# Gateway.net
KiCad netlist of a schematic drawn in EAGLE
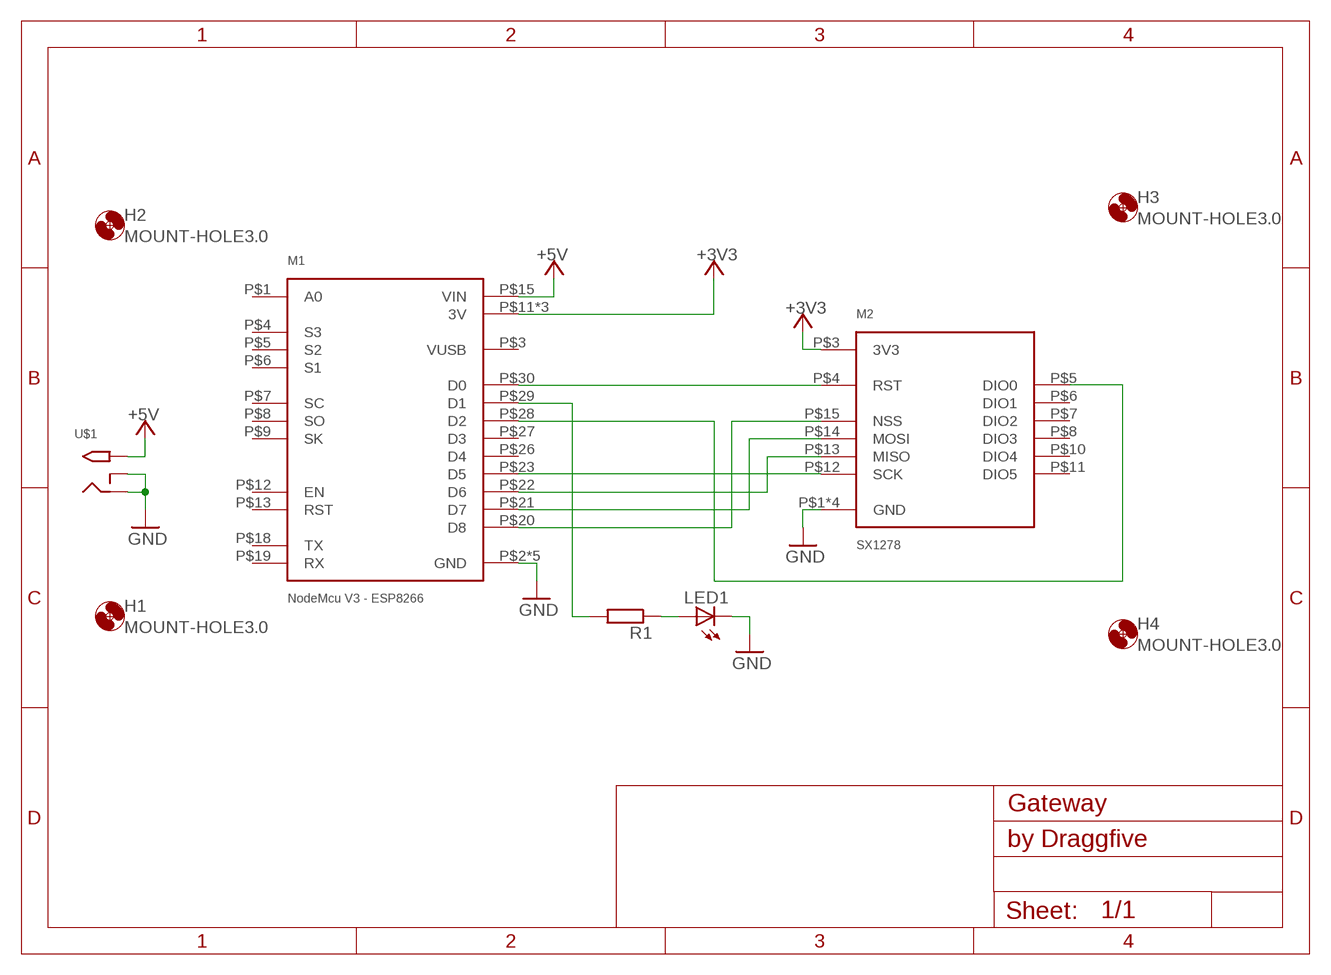
[diagram p0: schematic, sheet 1]

(export (version "E")
  (design (tool "Eeschema 10.0.6"))
  (components
    (comp (ref "H1")
      (value "MOUNT-HOLE3.0")
      (footprint "eagle-import:3,0")
      (libsource (lib "eagle-import") (part "MOUNT-HOLE3.0"))
    )
    (comp (ref "H2")
      (value "MOUNT-HOLE3.0")
      (footprint "eagle-import:3,0")
      (libsource (lib "eagle-import") (part "MOUNT-HOLE3.0"))
    )
    (comp (ref "H3")
      (value "MOUNT-HOLE3.0")
      (footprint "eagle-import:3,0")
      (libsource (lib "eagle-import") (part "MOUNT-HOLE3.0"))
    )
    (comp (ref "H4")
      (value "MOUNT-HOLE3.0")
      (footprint "eagle-import:3,0")
      (libsource (lib "eagle-import") (part "MOUNT-HOLE3.0"))
    )
    (comp (ref "LED1")
      (value "LED5MM")
      (footprint "eagle-import:LED5MM")
      (libsource (lib "eagle-import") (part "LED5MM"))
    )
    (comp (ref "M1")
      (value "NodeMcu V3 - ESP8266")
      (footprint "eagle-import:NODEMCU_V3")
      (libsource (lib "eagle-import") (part "NODEMCU_V3"))
    )
    (comp (ref "M2")
      (value "SX1278")
      (footprint "eagle-import:SX1278")
      (libsource (lib "eagle-import") (part "SX1278"))
    )
    (comp (ref "R1")
      (value "R-EU_0207/10")
      (footprint "eagle-import:0207_10")
      (libsource (lib "eagle-import") (part "R-EU_0207/10"))
    )
    (comp (ref "U$1")
      (value "2.1MMJACKTHM")
      (footprint "eagle-import:PJ-102A")
      (libsource (lib "eagle-import") (part "2.1MMJACKTHM"))
    )
  )
  (nets
    (net (code "1") (name "+3V3") (class "Default")
      (node (ref "M1") (pin "P$11") (pinfunction "3V_P$11") (pintype "bidirectional"))
      (node (ref "M1") (pin "P$16") (pinfunction "3V_P$16") (pintype "bidirectional"))
      (node (ref "M1") (pin "P$25") (pinfunction "3V_P$25") (pintype "bidirectional"))
      (node (ref "M2") (pin "P$3") (pinfunction "3V3_P$3") (pintype "bidirectional"))
    )
    (net (code "2") (name "+5V") (class "Default")
      (node (ref "M1") (pin "P$15") (pinfunction "VIN_P$15") (pintype "bidirectional"))
      (node (ref "U$1") (pin "TIP") (pinfunction "TIP_TIP") (pintype "bidirectional"))
    )
    (net (code "3") (name "GND") (class "Default")
      (node (ref "LED1") (pin "K") (pinfunction "C_K") (pintype "passive"))
      (node (ref "M1") (pin "P$10") (pinfunction "GND_P$10") (pintype "bidirectional"))
      (node (ref "M1") (pin "P$14") (pinfunction "GND_P$14") (pintype "bidirectional"))
      (node (ref "M1") (pin "P$17") (pinfunction "GND_P$17") (pintype "bidirectional"))
      (node (ref "M1") (pin "P$2") (pinfunction "GND_P$2") (pintype "bidirectional"))
      (node (ref "M1") (pin "P$24") (pinfunction "GND_P$24") (pintype "bidirectional"))
      (node (ref "M2") (pin "P$1") (pinfunction "GND_P$1") (pintype "bidirectional"))
      (node (ref "M2") (pin "P$16") (pinfunction "GND_P$16") (pintype "bidirectional"))
      (node (ref "M2") (pin "P$2") (pinfunction "GND_P$2") (pintype "bidirectional"))
      (node (ref "M2") (pin "P$9") (pinfunction "GND_P$9") (pintype "bidirectional"))
      (node (ref "U$1") (pin "RING") (pinfunction "RING_RING") (pintype "bidirectional"))
      (node (ref "U$1") (pin "RING_SW") (pinfunction "RING_SW_RING_SW") (pintype "bidirectional"))
    )
    (net (code "4") (name "Net-(LED1-PadA)") (class "Default")
      (node (ref "LED1") (pin "A") (pinfunction "A_A") (pintype "passive"))
      (node (ref "R1") (pin "1") (pinfunction "1_1") (pintype "passive"))
    )
    (net (code "5") (name "Net-(M1-D0)") (class "Default")
      (node (ref "M1") (pin "P$30") (pinfunction "D0_P$30") (pintype "bidirectional"))
      (node (ref "M2") (pin "P$4") (pinfunction "RST_P$4") (pintype "bidirectional"))
    )
    (net (code "6") (name "Net-(M1-D1)") (class "Default")
      (node (ref "M1") (pin "P$29") (pinfunction "D1_P$29") (pintype "bidirectional"))
      (node (ref "R1") (pin "2") (pinfunction "2_2") (pintype "passive"))
    )
    (net (code "7") (name "Net-(M1-D2)") (class "Default")
      (node (ref "M1") (pin "P$28") (pinfunction "D2_P$28") (pintype "bidirectional"))
      (node (ref "M2") (pin "P$5") (pinfunction "DIO0_P$5") (pintype "bidirectional"))
    )
    (net (code "8") (name "Net-(M1-D5)") (class "Default")
      (node (ref "M1") (pin "P$23") (pinfunction "D5_P$23") (pintype "bidirectional"))
      (node (ref "M2") (pin "P$12") (pinfunction "SCK_P$12") (pintype "bidirectional"))
    )
    (net (code "9") (name "Net-(M1-D6)") (class "Default")
      (node (ref "M1") (pin "P$22") (pinfunction "D6_P$22") (pintype "bidirectional"))
      (node (ref "M2") (pin "P$13") (pinfunction "MISO_P$13") (pintype "bidirectional"))
    )
    (net (code "10") (name "Net-(M1-D7)") (class "Default")
      (node (ref "M1") (pin "P$21") (pinfunction "D7_P$21") (pintype "bidirectional"))
      (node (ref "M2") (pin "P$14") (pinfunction "MOSI_P$14") (pintype "bidirectional"))
    )
    (net (code "11") (name "Net-(M1-D8)") (class "Default")
      (node (ref "M1") (pin "P$20") (pinfunction "D8_P$20") (pintype "bidirectional"))
      (node (ref "M2") (pin "P$15") (pinfunction "NSS_P$15") (pintype "bidirectional"))
    )
    (net (code "12") (name "unconnected-(M1-A0-PadP$1)") (class "Default")
      (node (ref "M1") (pin "P$1") (pinfunction "A0_P$1") (pintype "bidirectional"))
    )
    (net (code "13") (name "unconnected-(M1-D3-PadP$27)") (class "Default")
      (node (ref "M1") (pin "P$27") (pinfunction "D3_P$27") (pintype "bidirectional"))
    )
    (net (code "14") (name "unconnected-(M1-D4-PadP$26)") (class "Default")
      (node (ref "M1") (pin "P$26") (pinfunction "D4_P$26") (pintype "bidirectional"))
    )
    (net (code "15") (name "unconnected-(M1-EN-PadP$12)") (class "Default")
      (node (ref "M1") (pin "P$12") (pinfunction "EN_P$12") (pintype "bidirectional"))
    )
    (net (code "16") (name "unconnected-(M1-RST-PadP$13)") (class "Default")
      (node (ref "M1") (pin "P$13") (pinfunction "RST_P$13") (pintype "bidirectional"))
    )
    (net (code "17") (name "unconnected-(M1-RX-PadP$19)") (class "Default")
      (node (ref "M1") (pin "P$19") (pinfunction "RX_P$19") (pintype "bidirectional"))
    )
    (net (code "18") (name "unconnected-(M1-S1-PadP$6)") (class "Default")
      (node (ref "M1") (pin "P$6") (pinfunction "S1_P$6") (pintype "bidirectional"))
    )
    (net (code "19") (name "unconnected-(M1-S2-PadP$5)") (class "Default")
      (node (ref "M1") (pin "P$5") (pinfunction "S2_P$5") (pintype "bidirectional"))
    )
    (net (code "20") (name "unconnected-(M1-S3-PadP$4)") (class "Default")
      (node (ref "M1") (pin "P$4") (pinfunction "S3_P$4") (pintype "bidirectional"))
    )
    (net (code "21") (name "unconnected-(M1-SC-PadP$7)") (class "Default")
      (node (ref "M1") (pin "P$7") (pinfunction "SC_P$7") (pintype "bidirectional"))
    )
    (net (code "22") (name "unconnected-(M1-SK-PadP$9)") (class "Default")
      (node (ref "M1") (pin "P$9") (pinfunction "SK_P$9") (pintype "bidirectional"))
    )
    (net (code "23") (name "unconnected-(M1-SO-PadP$8)") (class "Default")
      (node (ref "M1") (pin "P$8") (pinfunction "SO_P$8") (pintype "bidirectional"))
    )
    (net (code "24") (name "unconnected-(M1-TX-PadP$18)") (class "Default")
      (node (ref "M1") (pin "P$18") (pinfunction "TX_P$18") (pintype "bidirectional"))
    )
    (net (code "25") (name "unconnected-(M1-VUSB-PadP$3)") (class "Default")
      (node (ref "M1") (pin "P$3") (pinfunction "VUSB_P$3") (pintype "bidirectional"))
    )
    (net (code "26") (name "unconnected-(M2-DIO1-PadP$6)") (class "Default")
      (node (ref "M2") (pin "P$6") (pinfunction "DIO1_P$6") (pintype "bidirectional"))
    )
    (net (code "27") (name "unconnected-(M2-DIO2-PadP$7)") (class "Default")
      (node (ref "M2") (pin "P$7") (pinfunction "DIO2_P$7") (pintype "bidirectional"))
    )
    (net (code "28") (name "unconnected-(M2-DIO3-PadP$8)") (class "Default")
      (node (ref "M2") (pin "P$8") (pinfunction "DIO3_P$8") (pintype "bidirectional"))
    )
    (net (code "29") (name "unconnected-(M2-DIO4-PadP$10)") (class "Default")
      (node (ref "M2") (pin "P$10") (pinfunction "DIO4_P$10") (pintype "bidirectional"))
    )
    (net (code "30") (name "unconnected-(M2-DIO5-PadP$11)") (class "Default")
      (node (ref "M2") (pin "P$11") (pinfunction "DIO5_P$11") (pintype "bidirectional"))
    )
  )
)
